# phantom_power.net
KiCad netlist of a schematic drawn in Altium Designer
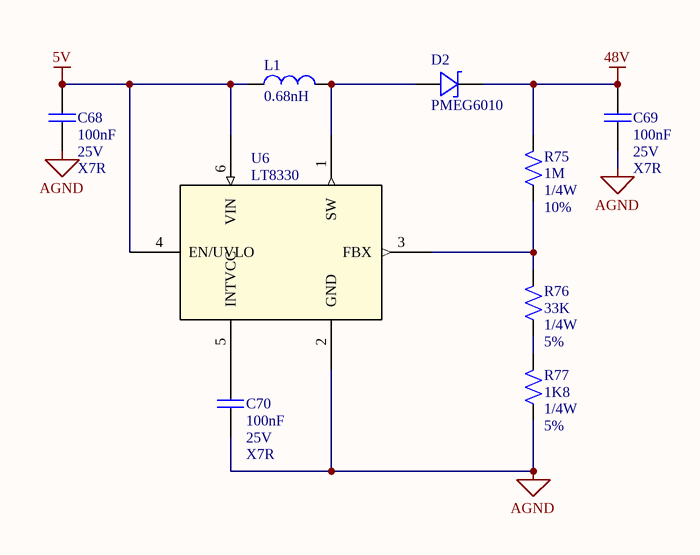
[diagram p0: phantom_power.SchDoc]

(export (version "E")
  (design (tool "Eeschema 10.0.6"))
  (components
    (comp (ref "C68")
      (value "Capacitor")
      (footprint "C0805")
      (description "Capacitor de placas paralelas")
      (fields (field (name "VALOR") "100nF") (field (name "TENSION") "25V") (field (name "TOLERANCIA") "X7R"))
      (libsource (lib "Sch_Comunes") (part "Capacitor"))
    )
    (comp (ref "C69")
      (value "Capacitor")
      (footprint "C0805")
      (description "Capacitor de placas paralelas")
      (fields (field (name "VALOR") "100nF") (field (name "TENSION") "25V") (field (name "TOLERANCIA") "X7R"))
      (libsource (lib "Sch_Comunes") (part "Capacitor"))
    )
    (comp (ref "C70")
      (value "Capacitor")
      (footprint "C0805")
      (description "Capacitor de placas paralelas")
      (fields (field (name "VALOR") "100nF") (field (name "TENSION") "25V") (field (name "TOLERANCIA") "X7R"))
      (libsource (lib "Sch_Comunes") (part "Capacitor"))
    )
    (comp (ref "D2")
      (value "PMEG6010")
      (footprint "SOD128")
      (libsource (lib "sch_comunes") (part "Schottky Diode"))
    )
    (comp (ref "L1") (value "0.68nH") (footprint "L0805") (libsource (lib "sch_comunes") (part "Inductor")))
    (comp (ref "R75")
      (value "Resistor")
      (footprint "R0805")
      (description "Resistencia")
      (fields (field (name "VALOR") "1M") (field (name "POTENCIA") "1/4W") (field (name "TOLERANCIA") "10%"))
      (libsource (lib "sch_comunes") (part "Resistor"))
    )
    (comp (ref "R76")
      (value "Resistor")
      (footprint "R0805")
      (description "Resistencia")
      (fields (field (name "VALOR") "33K") (field (name "POTENCIA") "1/4W") (field (name "TOLERANCIA") "5%"))
      (libsource (lib "sch_comunes") (part "Resistor"))
    )
    (comp (ref "R77")
      (value "Resistor")
      (footprint "R0805")
      (description "Resistencia")
      (fields (field (name "VALOR") "1K8") (field (name "POTENCIA") "1/4W") (field (name "TOLERANCIA") "5%"))
      (libsource (lib "sch_comunes") (part "Resistor"))
    )
    (comp (ref "U6")
      (value "LT8330")
      (footprint "S6")
      (description "Low IQ Boost/SEPIC/Inverting Converter with 1A, 60V Switch")
      (libsource (lib "Sch_DCDC") (part "LT8330"))
    )
  )
  (nets
    (net (code "1") (name "5V") (class "Default")
      (node (ref "C68") (pin "1") (pinfunction "1_1") (pintype "passive"))
      (node (ref "L1") (pin "1") (pinfunction "1_1") (pintype "passive"))
      (node (ref "U6") (pin "4") (pinfunction "EN/UVLO_4") (pintype "passive"))
      (node (ref "U6") (pin "6") (pinfunction "VIN_6") (pintype "input"))
    )
    (net (code "2") (name "48V") (class "Default")
      (node (ref "C69") (pin "1") (pinfunction "1_1") (pintype "passive"))
      (node (ref "D2") (pin "1") (pintype "passive"))
      (node (ref "R75") (pin "2") (pinfunction "2_2") (pintype "passive"))
    )
    (net (code "3") (name "AGND") (class "Default")
      (node (ref "C68") (pin "2") (pinfunction "2_2") (pintype "passive"))
      (node (ref "C69") (pin "2") (pinfunction "2_2") (pintype "passive"))
      (node (ref "C70") (pin "2") (pinfunction "2_2") (pintype "passive"))
      (node (ref "R77") (pin "1") (pinfunction "1_1") (pintype "passive"))
      (node (ref "U6") (pin "2") (pinfunction "GND_2") (pintype "power_in"))
    )
    (net (code "4") (name "Net-(R76-Pad1)") (class "Default")
      (node (ref "R76") (pin "1") (pinfunction "1_1") (pintype "passive"))
      (node (ref "R77") (pin "2") (pinfunction "2_2") (pintype "passive"))
    )
    (net (code "5") (name "Net-(U6-FBX)") (class "Default")
      (node (ref "R75") (pin "1") (pinfunction "1_1") (pintype "passive"))
      (node (ref "R76") (pin "2") (pinfunction "2_2") (pintype "passive"))
      (node (ref "U6") (pin "3") (pinfunction "FBX_3") (pintype "output"))
    )
    (net (code "6") (name "Net-(U6-INTVCC)") (class "Default")
      (node (ref "C70") (pin "1") (pinfunction "1_1") (pintype "passive"))
      (node (ref "U6") (pin "5") (pinfunction "INTVCC_5") (pintype "passive"))
    )
    (net (code "7") (name "Net-(U6-SW)") (class "Default")
      (node (ref "D2") (pin "2") (pintype "passive"))
      (node (ref "L1") (pin "2") (pinfunction "2_2") (pintype "passive"))
      (node (ref "U6") (pin "1") (pinfunction "SW_1") (pintype "output"))
    )
  )
)
